# MCU-io.net
KiCad netlist of a schematic drawn in Altium Designer
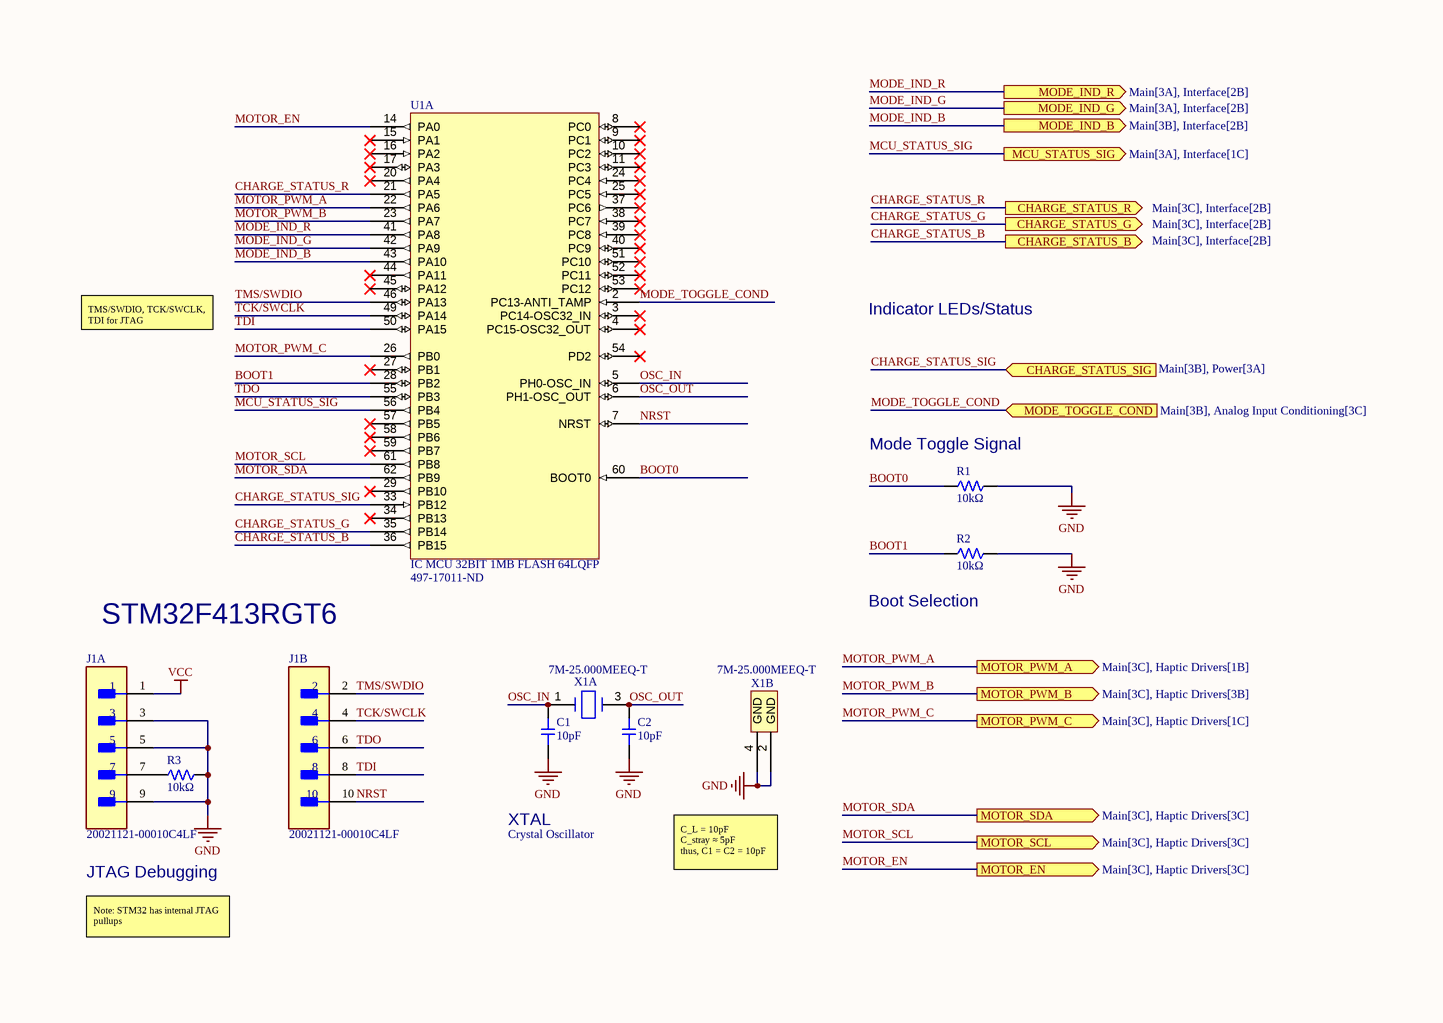
[diagram p0: MCU-io.SchDoc]

(export (version "E")
  (design (tool "Eeschema 10.0.6"))
  (components
    (comp (ref "C1")
      (value "CL10C100JB8NNNC")
      (footprint "CAP-0603")
      (description "Capacitor, Ceramic (MLCC), 10pF, ±5%, 50V, C0G, ±5%, SMD 0603")
      (fields
        (field (name "JLCPCB BASIC PART") "Yes")
        (field (name "CAPACITANCE") "10pF")
        (field (name "JLCPCB PART NUMBER") "C1634")
      )
      (libsource (lib "JLCCapacitor") (part "CL10C100JB8NNNC"))
    )
    (comp (ref "C2")
      (value "CL10C100JB8NNNC")
      (footprint "CAP-0603")
      (description "Capacitor, Ceramic (MLCC), 10pF, ±5%, 50V, C0G, ±5%, SMD 0603")
      (fields
        (field (name "JLCPCB BASIC PART") "Yes")
        (field (name "CAPACITANCE") "10pF")
        (field (name "JLCPCB PART NUMBER") "C1634")
      )
      (libsource (lib "JLCCapacitor") (part "CL10C100JB8NNNC"))
    )
    (comp (ref "J1")
      (value "20021121-00010C4LF")
      (footprint "FP-20021121-00010C4LF-MFG")
      (libsource (lib "Altium Content Vault") (part "544f42128f4185dcb88ce1ce9bf1982"))
    )
    (comp (ref "R1")
      (value "0603WAF1002T5E")
      (footprint "RES-0603")
      (description "Resistor, 10kΩ, ±1%, 100mW, 75V, ±100ppm/℃, -55℃~+155℃, SMD 0603")
      (fields
        (field (name "MANUFACTURER") "Uniroyal")
        (field (name "JLCPCB PART NUMBER") "C25804")
        (field (name "RESISTANCE") "10kΩ")
      )
      (libsource (lib "JLCResistor") (part "0603WAF1002T5E"))
    )
    (comp (ref "R2")
      (value "0603WAF1002T5E")
      (footprint "RES-0603")
      (description "Resistor, 10kΩ, ±1%, 100mW, 75V, ±100ppm/℃, -55℃~+155℃, SMD 0603")
      (fields
        (field (name "MANUFACTURER") "Uniroyal")
        (field (name "JLCPCB PART NUMBER") "C25804")
        (field (name "RESISTANCE") "10kΩ")
      )
      (libsource (lib "JLCResistor") (part "0603WAF1002T5E"))
    )
    (comp (ref "R3")
      (value "0603WAF1002T5E")
      (footprint "RES-0603")
      (description "Resistor, 10kΩ, ±1%, 100mW, 75V, ±100ppm/℃, -55℃~+155℃, SMD 0603")
      (fields
        (field (name "MANUFACTURER") "Uniroyal")
        (field (name "JLCPCB PART NUMBER") "C25804")
        (field (name "RESISTANCE") "10kΩ")
      )
      (libsource (lib "JLCResistor") (part "0603WAF1002T5E"))
    )
    (comp (ref "U1")
      (value "IC MCU 32BIT 1MB FLASH 64LQFP")
      (footprint "LQFP64-10x10mm")
      (description "ARM® Cortex®-M4 STM32F4 Microcontroller IC 32-Bit 100MHz 1MB (1M x 8) FLASH 64-LQFP (10x10)")
      (fields
        (field (name "MANUFACTURER_PART_NUMBER") "stm32f4xxr2")
        (field (name "SUPPLIER PART NUMBER 1") "497-17011-ND")
        (field (name "COPYRIGHT") "Copyright (C) 2016 Accelerated Designs. All rights reserved")
      )
      (libsource (lib "Misc") (part "STM32F4xxR2_minimalist"))
    )
    (comp (ref "X1")
      (value "7M-25.000MEEQ-T")
      (footprint "OSCSC320X250X100N")
      (description "CRYSTAL 25.0000MHZ 10PF SMD")
      (fields (field (name "TOLERANCE") "10ppm"))
      (libsource (lib "") (part "7M-25.000MEEQ-T_1"))
    )
  )
  (nets
    (net (code "1") (name "/BOOT0") (class "Default")
      (node (ref "R1") (pin "1") (pinfunction "1_1") (pintype "passive"))
      (node (ref "U1") (pin "60") (pinfunction "BOOT0_60") (pintype "input"))
    )
    (net (code "2") (name "/BOOT1") (class "Default")
      (node (ref "R2") (pin "1") (pinfunction "1_1") (pintype "passive"))
      (node (ref "U1") (pin "28") (pinfunction "PB2_28") (pintype "bidirectional"))
    )
    (net (code "3") (name "/CHARGE_STATUS_B") (class "Default")
      (node (ref "U1") (pin "36") (pinfunction "PB15_36") (pintype "output"))
    )
    (net (code "4") (name "/CHARGE_STATUS_G") (class "Default")
      (node (ref "U1") (pin "35") (pinfunction "PB14_35") (pintype "output"))
    )
    (net (code "5") (name "/CHARGE_STATUS_R") (class "Default")
      (node (ref "U1") (pin "21") (pinfunction "PA5_21") (pintype "output"))
    )
    (net (code "6") (name "/CHARGE_STATUS_SIG") (class "Default")
      (node (ref "U1") (pin "33") (pinfunction "PB12_33") (pintype "input"))
    )
    (net (code "7") (name "/MCU_STATUS_SIG") (class "Default")
      (node (ref "U1") (pin "56") (pinfunction "PB4_56") (pintype "output"))
    )
    (net (code "8") (name "/MODE_IND_B") (class "Default")
      (node (ref "U1") (pin "43") (pinfunction "PA10_43") (pintype "output"))
    )
    (net (code "9") (name "/MODE_IND_G") (class "Default")
      (node (ref "U1") (pin "42") (pinfunction "PA9_42") (pintype "output"))
    )
    (net (code "10") (name "/MODE_IND_R") (class "Default")
      (node (ref "U1") (pin "41") (pinfunction "PA8_41") (pintype "output"))
    )
    (net (code "11") (name "/MODE_TOGGLE_COND") (class "Default")
      (node (ref "U1") (pin "2") (pinfunction "PC13-ANTI_TAMP_2") (pintype "input"))
    )
    (net (code "12") (name "/MOTOR_EN") (class "Default")
      (node (ref "U1") (pin "14") (pinfunction "PA0_14") (pintype "output"))
    )
    (net (code "13") (name "/MOTOR_PWM_A") (class "Default")
      (node (ref "U1") (pin "22") (pinfunction "PA6_22") (pintype "output"))
    )
    (net (code "14") (name "/MOTOR_PWM_B") (class "Default")
      (node (ref "U1") (pin "23") (pinfunction "PA7_23") (pintype "output"))
    )
    (net (code "15") (name "/MOTOR_PWM_C") (class "Default")
      (node (ref "U1") (pin "26") (pinfunction "PB0_26") (pintype "output"))
    )
    (net (code "16") (name "/MOTOR_SCL") (class "Default")
      (node (ref "U1") (pin "61") (pinfunction "PB8_61") (pintype "output"))
    )
    (net (code "17") (name "/MOTOR_SDA") (class "Default")
      (node (ref "U1") (pin "62") (pinfunction "PB9_62") (pintype "output"))
    )
    (net (code "18") (name "/NRST") (class "Default")
      (node (ref "J1") (pin "10") (pinfunction "10_10") (pintype "passive"))
      (node (ref "U1") (pin "7") (pinfunction "NRST_7") (pintype "bidirectional"))
    )
    (net (code "19") (name "/OSC_IN") (class "Default")
      (node (ref "C1") (pin "2") (pinfunction "2_2") (pintype "passive"))
      (node (ref "U1") (pin "5") (pinfunction "PH0-OSC_IN_5") (pintype "bidirectional"))
      (node (ref "X1") (pin "1") (pinfunction "11_1") (pintype "passive"))
    )
    (net (code "20") (name "/OSC_OUT") (class "Default")
      (node (ref "C2") (pin "2") (pinfunction "2_2") (pintype "passive"))
      (node (ref "U1") (pin "6") (pinfunction "PH1-OSC_OUT_6") (pintype "bidirectional"))
      (node (ref "X1") (pin "3") (pintype "passive"))
    )
    (net (code "21") (name "/TCK{slash}SWCLK") (class "Default")
      (node (ref "J1") (pin "4") (pinfunction "4_4") (pintype "passive"))
      (node (ref "U1") (pin "49") (pinfunction "PA14_49") (pintype "bidirectional"))
    )
    (net (code "22") (name "/TDI") (class "Default")
      (node (ref "J1") (pin "8") (pinfunction "8_8") (pintype "passive"))
      (node (ref "U1") (pin "50") (pinfunction "PA15_50") (pintype "bidirectional"))
    )
    (net (code "23") (name "/TDO") (class "Default")
      (node (ref "J1") (pin "6") (pinfunction "6_6") (pintype "passive"))
      (node (ref "U1") (pin "55") (pinfunction "PB3_55") (pintype "bidirectional"))
    )
    (net (code "24") (name "/TMS{slash}SWDIO") (class "Default")
      (node (ref "J1") (pin "2") (pinfunction "2_2") (pintype "passive"))
      (node (ref "U1") (pin "46") (pinfunction "PA13_46") (pintype "bidirectional"))
    )
    (net (code "25") (name "GND") (class "Default")
      (node (ref "C1") (pin "1") (pinfunction "1_1") (pintype "passive"))
      (node (ref "C2") (pin "1") (pinfunction "1_1") (pintype "passive"))
      (node (ref "J1") (pin "3") (pinfunction "3_3") (pintype "passive"))
      (node (ref "J1") (pin "5") (pinfunction "5_5") (pintype "passive"))
      (node (ref "J1") (pin "9") (pinfunction "9_9") (pintype "passive"))
      (node (ref "R1") (pin "2") (pinfunction "2_2") (pintype "passive"))
      (node (ref "R2") (pin "2") (pinfunction "2_2") (pintype "passive"))
      (node (ref "R3") (pin "2") (pinfunction "2_2") (pintype "passive"))
      (node (ref "X1") (pin "2") (pinfunction "GND_2") (pintype "passive"))
      (node (ref "X1") (pin "4") (pinfunction "GND_4") (pintype "passive"))
    )
    (net (code "26") (name "Net-(J1-Pad7)") (class "Default")
      (node (ref "J1") (pin "7") (pinfunction "7_7") (pintype "passive"))
      (node (ref "R3") (pin "1") (pinfunction "1_1") (pintype "passive"))
    )
    (net (code "27") (name "VCC") (class "Default")
      (node (ref "J1") (pin "1") (pinfunction "1_1") (pintype "passive"))
    )
    (net (code "28") (name "unconnected-(U1A-PA1-Pad15)") (class "Default")
      (node (ref "U1") (pin "15") (pinfunction "PA1_15") (pintype "input+no_connect"))
    )
    (net (code "29") (name "unconnected-(U1A-PA2-Pad16)") (class "Default")
      (node (ref "U1") (pin "16") (pinfunction "PA2_16") (pintype "input+no_connect"))
    )
    (net (code "30") (name "unconnected-(U1A-PA3-Pad17)") (class "Default")
      (node (ref "U1") (pin "17") (pinfunction "PA3_17") (pintype "bidirectional+no_connect"))
    )
    (net (code "31") (name "unconnected-(U1A-PA4-Pad20)") (class "Default")
      (node (ref "U1") (pin "20") (pinfunction "PA4_20") (pintype "output+no_connect"))
    )
    (net (code "32") (name "unconnected-(U1A-PA11-Pad44)") (class "Default")
      (node (ref "U1") (pin "44") (pinfunction "PA11_44") (pintype "output+no_connect"))
    )
    (net (code "33") (name "unconnected-(U1A-PA12-Pad45)") (class "Default")
      (node (ref "U1") (pin "45") (pinfunction "PA12_45") (pintype "bidirectional+no_connect"))
    )
    (net (code "34") (name "unconnected-(U1A-PB1-Pad27)") (class "Default")
      (node (ref "U1") (pin "27") (pinfunction "PB1_27") (pintype "bidirectional+no_connect"))
    )
    (net (code "35") (name "unconnected-(U1A-PB5-Pad57)") (class "Default")
      (node (ref "U1") (pin "57") (pinfunction "PB5_57") (pintype "output+no_connect"))
    )
    (net (code "36") (name "unconnected-(U1A-PB6-Pad58)") (class "Default")
      (node (ref "U1") (pin "58") (pinfunction "PB6_58") (pintype "output+no_connect"))
    )
    (net (code "37") (name "unconnected-(U1A-PB7-Pad59)") (class "Default")
      (node (ref "U1") (pin "59") (pinfunction "PB7_59") (pintype "output+no_connect"))
    )
    (net (code "38") (name "unconnected-(U1A-PB10-Pad29)") (class "Default")
      (node (ref "U1") (pin "29") (pinfunction "PB10_29") (pintype "output+no_connect"))
    )
    (net (code "39") (name "unconnected-(U1A-PB13-Pad34)") (class "Default")
      (node (ref "U1") (pin "34") (pinfunction "PB13_34") (pintype "output+no_connect"))
    )
    (net (code "40") (name "unconnected-(U1A-PC0-Pad8)") (class "Default")
      (node (ref "U1") (pin "8") (pinfunction "PC0_8") (pintype "bidirectional+no_connect"))
    )
    (net (code "41") (name "unconnected-(U1A-PC1-Pad9)") (class "Default")
      (node (ref "U1") (pin "9") (pinfunction "PC1_9") (pintype "bidirectional+no_connect"))
    )
    (net (code "42") (name "unconnected-(U1A-PC2-Pad10)") (class "Default")
      (node (ref "U1") (pin "10") (pinfunction "PC2_10") (pintype "bidirectional+no_connect"))
    )
    (net (code "43") (name "unconnected-(U1A-PC3-Pad11)") (class "Default")
      (node (ref "U1") (pin "11") (pinfunction "PC3_11") (pintype "bidirectional+no_connect"))
    )
    (net (code "44") (name "unconnected-(U1A-PC4-Pad24)") (class "Default")
      (node (ref "U1") (pin "24") (pinfunction "PC4_24") (pintype "input+no_connect"))
    )
    (net (code "45") (name "unconnected-(U1A-PC5-Pad25)") (class "Default")
      (node (ref "U1") (pin "25") (pinfunction "PC5_25") (pintype "input+no_connect"))
    )
    (net (code "46") (name "unconnected-(U1A-PC6-Pad37)") (class "Default")
      (node (ref "U1") (pin "37") (pinfunction "PC6_37") (pintype "output+no_connect"))
    )
    (net (code "47") (name "unconnected-(U1A-PC7-Pad38)") (class "Default")
      (node (ref "U1") (pin "38") (pinfunction "PC7_38") (pintype "input+no_connect"))
    )
    (net (code "48") (name "unconnected-(U1A-PC8-Pad39)") (class "Default")
      (node (ref "U1") (pin "39") (pinfunction "PC8_39") (pintype "input+no_connect"))
    )
    (net (code "49") (name "unconnected-(U1A-PC9-Pad40)") (class "Default")
      (node (ref "U1") (pin "40") (pinfunction "PC9_40") (pintype "bidirectional+no_connect"))
    )
    (net (code "50") (name "unconnected-(U1A-PC10-Pad51)") (class "Default")
      (node (ref "U1") (pin "51") (pinfunction "PC10_51") (pintype "bidirectional+no_connect"))
    )
    (net (code "51") (name "unconnected-(U1A-PC11-Pad52)") (class "Default")
      (node (ref "U1") (pin "52") (pinfunction "PC11_52") (pintype "bidirectional+no_connect"))
    )
    (net (code "52") (name "unconnected-(U1A-PC12-Pad53)") (class "Default")
      (node (ref "U1") (pin "53") (pinfunction "PC12_53") (pintype "bidirectional+no_connect"))
    )
    (net (code "53") (name "unconnected-(U1A-PC14-OSC32_IN-Pad3)") (class "Default")
      (node (ref "U1") (pin "3") (pinfunction "PC14-OSC32_IN_3") (pintype "bidirectional+no_connect"))
    )
    (net (code "54") (name "unconnected-(U1A-PC15-OSC32_OUT-Pad4)") (class "Default")
      (node (ref "U1") (pin "4") (pinfunction "PC15-OSC32_OUT_4") (pintype "bidirectional+no_connect"))
    )
    (net (code "55") (name "unconnected-(U1A-PD2-Pad54)") (class "Default")
      (node (ref "U1") (pin "54") (pinfunction "PD2_54") (pintype "bidirectional+no_connect"))
    )
  )
)
